# Lumiboard_-_main_board_rev_C.net
KiCad netlist of a schematic drawn in EAGLE
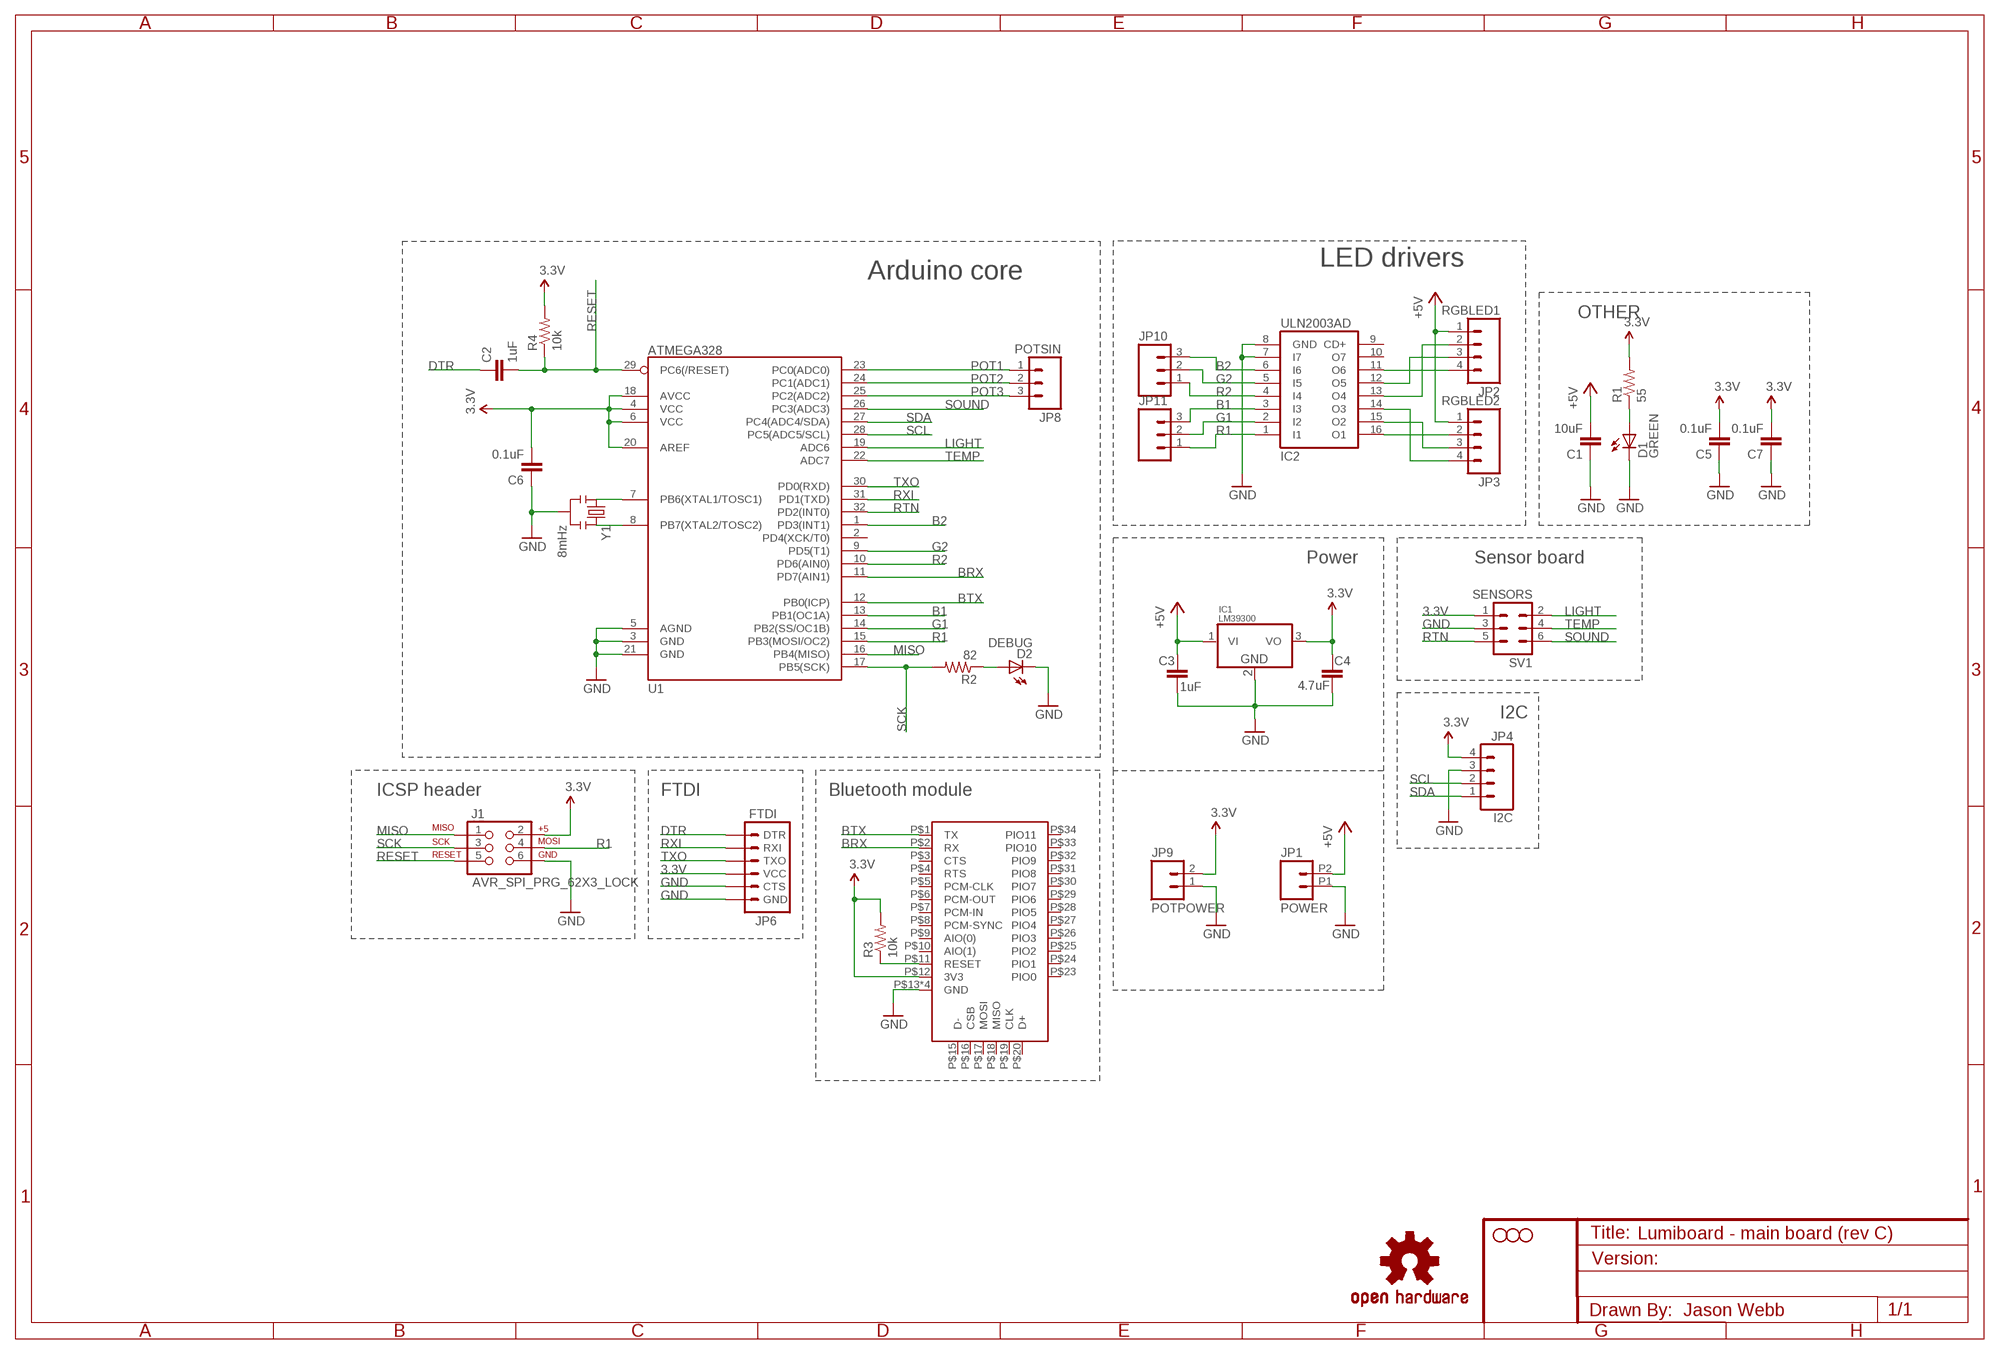
[diagram p0: schematic, sheet 1]

(export (version "E")
  (design (tool "Eeschema 10.0.6"))
  (components
    (comp (ref "C1")
      (value "10uF")
      (footprint "eagle-import:0805")
      (libsource (lib "eagle-import") (part "CAP0805"))
    )
    (comp (ref "C2")
      (value "1uF")
      (footprint "eagle-import:0805")
      (libsource (lib "eagle-import") (part "CAP0805"))
    )
    (comp (ref "C3")
      (value "1uF")
      (footprint "eagle-import:0805")
      (libsource (lib "eagle-import") (part "CAP0805"))
    )
    (comp (ref "C4")
      (value "4.7uF")
      (footprint "eagle-import:0805")
      (libsource (lib "eagle-import") (part "CAP0805"))
    )
    (comp (ref "C5")
      (value "0.1uF")
      (footprint "eagle-import:0805")
      (libsource (lib "eagle-import") (part "CAP0805"))
    )
    (comp (ref "C6")
      (value "0.1uF")
      (footprint "eagle-import:0805")
      (libsource (lib "eagle-import") (part "CAP0805"))
    )
    (comp (ref "C7")
      (value "0.1uF")
      (footprint "eagle-import:0805")
      (libsource (lib "eagle-import") (part "CAP0805"))
    )
    (comp (ref "D1")
      (value "GREEN")
      (footprint "eagle-import:CHIPLED_0805")
      (libsource (lib "eagle-import") (part "LEDCHIPLED_0805"))
    )
    (comp (ref "D2")
      (value "DEBUG")
      (footprint "eagle-import:CHIPLED_0805")
      (libsource (lib "eagle-import") (part "LEDCHIPLED_0805"))
    )
    (comp (ref "H1")
      (value "STAND-OFFTIGHT")
      (footprint "eagle-import:STAND-OFF-TIGHT")
      (libsource (lib "eagle-import") (part "STAND-OFFTIGHT"))
    )
    (comp (ref "H2")
      (value "STAND-OFFTIGHT")
      (footprint "eagle-import:STAND-OFF-TIGHT")
      (libsource (lib "eagle-import") (part "STAND-OFFTIGHT"))
    )
    (comp (ref "H3")
      (value "STAND-OFFTIGHT")
      (footprint "eagle-import:STAND-OFF-TIGHT")
      (libsource (lib "eagle-import") (part "STAND-OFFTIGHT"))
    )
    (comp (ref "IC1")
      (value "LM39300")
      (footprint "eagle-import:DPAK")
      (libsource (lib "eagle-import") (part "LM39300"))
    )
    (comp (ref "IC2")
      (value "ULN2003AD")
      (footprint "eagle-import:SO16")
      (libsource (lib "eagle-import") (part "ULN2003AD"))
    )
    (comp (ref "J1")
      (value "AVR_SPI_PRG_62X3_LOCK")
      (footprint "eagle-import:2X3_LOCK")
      (libsource (lib "eagle-import") (part "AVR_SPI_PRG_62X3_LOCK"))
    )
    (comp (ref "JP1")
      (value "POWER")
      (footprint "eagle-import:1X02_2.54_SCREWTERM")
      (libsource (lib "eagle-import") (part "M022.54MM_SCREWTERM"))
    )
    (comp (ref "JP2")
      (value "RGBLED1")
      (footprint "eagle-import:1X04")
      (libsource (lib "eagle-import") (part "M04PTH"))
    )
    (comp (ref "JP3")
      (value "RGBLED2")
      (footprint "eagle-import:1X04")
      (libsource (lib "eagle-import") (part "M04PTH"))
    )
    (comp (ref "JP4")
      (value "I2C")
      (footprint "eagle-import:1X04")
      (libsource (lib "eagle-import") (part "M04PTH"))
    )
    (comp (ref "JP6")
      (value "FTDI")
      (footprint "eagle-import:1X06_LOCK")
      (libsource (lib "eagle-import") (part "ARDUINO_SERIAL_PROGRAMLOCK"))
    )
    (comp (ref "JP8")
      (value "POTSIN")
      (footprint "eagle-import:1X03")
      (libsource (lib "eagle-import") (part "M03PTH"))
    )
    (comp (ref "JP9")
      (value "POTPOWER")
      (footprint "eagle-import:1X02")
      (libsource (lib "eagle-import") (part "M02PTH"))
    )
    (comp (ref "JP10")
      (value "M03PTH")
      (footprint "eagle-import:1X03")
      (libsource (lib "eagle-import") (part "SparkFun-Connectors_M03PTH"))
    )
    (comp (ref "JP11")
      (value "M03PTH")
      (footprint "eagle-import:1X03")
      (libsource (lib "eagle-import") (part "SparkFun-Connectors_M03PTH"))
    )
    (comp (ref "LOGO1")
      (value "OSHW-LOGOS")
      (footprint "eagle-import:OSHW-LOGO-S")
      (libsource (lib "eagle-import") (part "OSHW-LOGOS"))
    )
    (comp (ref "R1")
      (value "55")
      (footprint "eagle-import:0805")
      (libsource (lib "eagle-import") (part "RESISTOR0805-RES"))
    )
    (comp (ref "R2")
      (value "82")
      (footprint "eagle-import:0805")
      (libsource (lib "eagle-import") (part "RESISTOR0805-RES"))
    )
    (comp (ref "R3")
      (value "10k")
      (footprint "eagle-import:0805")
      (libsource (lib "eagle-import") (part "RESISTOR0805-RES"))
    )
    (comp (ref "R4")
      (value "10k")
      (footprint "eagle-import:0805")
      (libsource (lib "eagle-import") (part "RESISTOR0805-RES"))
    )
    (comp (ref "SV1")
      (value "SENSORS")
      (footprint "eagle-import:ML6")
      (libsource (lib "eagle-import") (part "ML6"))
    )
    (comp (ref "U1")
      (value "ATMEGA328")
      (footprint "eagle-import:TQFP32-08")
      (libsource (lib "eagle-import") (part "ATMEGA168"))
    )
    (comp (ref "U2")
      (value "DX_BT_MODULE")
      (footprint "eagle-import:DXBLUETOOTHMODULE")
      (libsource (lib "eagle-import") (part "DX_BT_MODULE"))
    )
    (comp (ref "Y1")
      (value "8mHz")
      (footprint "eagle-import:RESONATOR-SMD")
      (libsource (lib "eagle-import") (part "RESONATORSMD"))
    )
  )
  (nets
    (net (code "1") (name "+5V") (class "Default")
      (node (ref "C1") (pin "2") (pinfunction "2_2") (pintype "passive"))
      (node (ref "C3") (pin "2") (pinfunction "2_2") (pintype "passive"))
      (node (ref "IC1") (pin "1") (pinfunction "VI_1") (pintype "input"))
      (node (ref "JP1") (pin "P2") (pinfunction "2_P2") (pintype "passive"))
      (node (ref "JP2") (pin "1") (pinfunction "1_1") (pintype "passive"))
      (node (ref "JP3") (pin "1") (pinfunction "1_1") (pintype "passive"))
    )
    (net (code "2") (name "/B1") (class "Default")
      (node (ref "IC2") (pin "3") (pinfunction "I3_3") (pintype "input"))
      (node (ref "JP11") (pin "3") (pinfunction "3_3") (pintype "passive"))
      (node (ref "U1") (pin "13") (pinfunction "PB1(OC1A)_13") (pintype "bidirectional"))
    )
    (net (code "3") (name "/B2") (class "Default")
      (node (ref "IC2") (pin "6") (pinfunction "I6_6") (pintype "input"))
      (node (ref "JP10") (pin "3") (pinfunction "3_3") (pintype "passive"))
      (node (ref "U1") (pin "1") (pinfunction "PD3(INT1)_1") (pintype "bidirectional"))
    )
    (net (code "4") (name "/BRX") (class "Default")
      (node (ref "U1") (pin "11") (pinfunction "PD7(AIN1)_11") (pintype "bidirectional"))
      (node (ref "U2") (pin "P$2") (pinfunction "RX_P$2") (pintype "input"))
    )
    (net (code "5") (name "/BTX") (class "Default")
      (node (ref "U1") (pin "12") (pinfunction "PB0(ICP)_12") (pintype "bidirectional"))
      (node (ref "U2") (pin "P$1") (pinfunction "TX_P$1") (pintype "output"))
    )
    (net (code "6") (name "/DTR") (class "Default")
      (node (ref "C2") (pin "1") (pinfunction "1_1") (pintype "passive"))
      (node (ref "JP6") (pin "1") (pinfunction "DTR_1") (pintype "passive"))
    )
    (net (code "7") (name "/G1") (class "Default")
      (node (ref "IC2") (pin "2") (pinfunction "I2_2") (pintype "input"))
      (node (ref "JP11") (pin "2") (pinfunction "2_2") (pintype "passive"))
      (node (ref "U1") (pin "14") (pinfunction "PB2(SS/OC1B)_14") (pintype "bidirectional"))
    )
    (net (code "8") (name "/G2") (class "Default")
      (node (ref "IC2") (pin "5") (pinfunction "I5_5") (pintype "input"))
      (node (ref "JP10") (pin "2") (pinfunction "2_2") (pintype "passive"))
      (node (ref "U1") (pin "9") (pinfunction "PD5(T1)_9") (pintype "bidirectional"))
    )
    (net (code "9") (name "/LIGHT") (class "Default")
      (node (ref "SV1") (pin "2") (pinfunction "2_2") (pintype "passive"))
      (node (ref "U1") (pin "19") (pinfunction "ADC6_19") (pintype "bidirectional"))
    )
    (net (code "10") (name "/MISO") (class "Default")
      (node (ref "J1") (pin "1") (pinfunction "1_1") (pintype "passive"))
      (node (ref "U1") (pin "16") (pinfunction "PB4(MISO)_16") (pintype "bidirectional"))
    )
    (net (code "11") (name "/POT1") (class "Default")
      (node (ref "JP8") (pin "1") (pinfunction "1_1") (pintype "passive"))
      (node (ref "U1") (pin "23") (pinfunction "PC0(ADC0)_23") (pintype "bidirectional"))
    )
    (net (code "12") (name "/POT2") (class "Default")
      (node (ref "JP8") (pin "2") (pinfunction "2_2") (pintype "passive"))
      (node (ref "U1") (pin "24") (pinfunction "PC1(ADC1)_24") (pintype "bidirectional"))
    )
    (net (code "13") (name "/POT3") (class "Default")
      (node (ref "JP8") (pin "3") (pinfunction "3_3") (pintype "passive"))
      (node (ref "U1") (pin "25") (pinfunction "PC2(ADC2)_25") (pintype "bidirectional"))
    )
    (net (code "14") (name "/R1") (class "Default")
      (node (ref "IC2") (pin "1") (pinfunction "I1_1") (pintype "input"))
      (node (ref "J1") (pin "4") (pinfunction "4_4") (pintype "passive"))
      (node (ref "JP11") (pin "1") (pinfunction "1_1") (pintype "passive"))
      (node (ref "U1") (pin "15") (pinfunction "PB3(MOSI/OC2)_15") (pintype "bidirectional"))
    )
    (net (code "15") (name "/R2") (class "Default")
      (node (ref "IC2") (pin "4") (pinfunction "I4_4") (pintype "input"))
      (node (ref "JP10") (pin "1") (pinfunction "1_1") (pintype "passive"))
      (node (ref "U1") (pin "10") (pinfunction "PD6(AIN0)_10") (pintype "bidirectional"))
    )
    (net (code "16") (name "/RESET") (class "Default")
      (node (ref "C2") (pin "2") (pinfunction "2_2") (pintype "passive"))
      (node (ref "J1") (pin "5") (pinfunction "5_5") (pintype "passive"))
      (node (ref "R4") (pin "1") (pinfunction "1_1") (pintype "passive"))
      (node (ref "U1") (pin "29") (pinfunction "PC6(/RESET)_29") (pintype "bidirectional"))
    )
    (net (code "17") (name "/RTN") (class "Default")
      (node (ref "SV1") (pin "5") (pinfunction "5_5") (pintype "passive"))
      (node (ref "U1") (pin "32") (pinfunction "PD2(INT0)_32") (pintype "bidirectional"))
    )
    (net (code "18") (name "/RXI") (class "Default")
      (node (ref "JP6") (pin "2") (pinfunction "RXI_2") (pintype "passive"))
      (node (ref "U1") (pin "31") (pinfunction "PD1(TXD)_31") (pintype "bidirectional"))
    )
    (net (code "19") (name "/SCK") (class "Default")
      (node (ref "J1") (pin "3") (pinfunction "3_3") (pintype "passive"))
      (node (ref "R2") (pin "2") (pinfunction "2_2") (pintype "passive"))
      (node (ref "U1") (pin "17") (pinfunction "PB5(SCK)_17") (pintype "bidirectional"))
    )
    (net (code "20") (name "/SCL") (class "Default")
      (node (ref "JP4") (pin "2") (pinfunction "2_2") (pintype "passive"))
      (node (ref "U1") (pin "28") (pinfunction "PC5(ADC5/SCL)_28") (pintype "bidirectional"))
    )
    (net (code "21") (name "/SDA") (class "Default")
      (node (ref "JP4") (pin "1") (pinfunction "1_1") (pintype "passive"))
      (node (ref "U1") (pin "27") (pinfunction "PC4(ADC4/SDA)_27") (pintype "bidirectional"))
    )
    (net (code "22") (name "/SOUND") (class "Default")
      (node (ref "SV1") (pin "6") (pinfunction "6_6") (pintype "passive"))
      (node (ref "U1") (pin "26") (pinfunction "PC3(ADC3)_26") (pintype "bidirectional"))
    )
    (net (code "23") (name "/TEMP") (class "Default")
      (node (ref "SV1") (pin "4") (pinfunction "4_4") (pintype "passive"))
      (node (ref "U1") (pin "22") (pinfunction "ADC7_22") (pintype "bidirectional"))
    )
    (net (code "24") (name "/TXO") (class "Default")
      (node (ref "JP6") (pin "3") (pinfunction "TXO_3") (pintype "passive"))
      (node (ref "U1") (pin "30") (pinfunction "PD0(RXD)_30") (pintype "bidirectional"))
    )
    (net (code "25") (name "3.3V") (class "Default")
      (node (ref "C4") (pin "2") (pinfunction "2_2") (pintype "passive"))
      (node (ref "C5") (pin "2") (pinfunction "2_2") (pintype "passive"))
      (node (ref "C6") (pin "2") (pinfunction "2_2") (pintype "passive"))
      (node (ref "C7") (pin "2") (pinfunction "2_2") (pintype "passive"))
      (node (ref "IC1") (pin "3") (pinfunction "VO_3") (pintype "bidirectional"))
      (node (ref "J1") (pin "2") (pinfunction "2_2") (pintype "passive"))
      (node (ref "JP4") (pin "4") (pinfunction "4_4") (pintype "passive"))
      (node (ref "JP6") (pin "4") (pinfunction "VCC_4") (pintype "passive"))
      (node (ref "JP9") (pin "2") (pinfunction "2_2") (pintype "passive"))
      (node (ref "R1") (pin "2") (pinfunction "2_2") (pintype "passive"))
      (node (ref "R3") (pin "2") (pinfunction "2_2") (pintype "passive"))
      (node (ref "R4") (pin "2") (pinfunction "2_2") (pintype "passive"))
      (node (ref "SV1") (pin "1") (pinfunction "1_1") (pintype "passive"))
      (node (ref "U1") (pin "18") (pinfunction "AVCC_18") (pintype "bidirectional"))
      (node (ref "U1") (pin "20") (pinfunction "AREF_20") (pintype "bidirectional"))
      (node (ref "U1") (pin "4") (pinfunction "VCC_4") (pintype "bidirectional"))
      (node (ref "U1") (pin "6") (pinfunction "VCC_6") (pintype "bidirectional"))
      (node (ref "U2") (pin "P$12") (pinfunction "3V3_P$12") (pintype "power_in"))
    )
    (net (code "26") (name "GND") (class "Default")
      (node (ref "C1") (pin "1") (pinfunction "1_1") (pintype "passive"))
      (node (ref "C3") (pin "1") (pinfunction "1_1") (pintype "passive"))
      (node (ref "C4") (pin "1") (pinfunction "1_1") (pintype "passive"))
      (node (ref "C5") (pin "1") (pinfunction "1_1") (pintype "passive"))
      (node (ref "C6") (pin "1") (pinfunction "1_1") (pintype "passive"))
      (node (ref "C7") (pin "1") (pinfunction "1_1") (pintype "passive"))
      (node (ref "D1") (pin "C") (pinfunction "C_C") (pintype "passive"))
      (node (ref "D2") (pin "C") (pinfunction "C_C") (pintype "passive"))
      (node (ref "IC1") (pin "2") (pinfunction "GND_2") (pintype "bidirectional"))
      (node (ref "IC2") (pin "7") (pinfunction "I7_7") (pintype "input"))
      (node (ref "IC2") (pin "8") (pinfunction "GND_8") (pintype "power_in"))
      (node (ref "J1") (pin "6") (pinfunction "6_6") (pintype "passive"))
      (node (ref "JP1") (pin "P1") (pinfunction "1_P1") (pintype "passive"))
      (node (ref "JP4") (pin "3") (pinfunction "3_3") (pintype "passive"))
      (node (ref "JP6") (pin "5") (pinfunction "CTS_5") (pintype "passive"))
      (node (ref "JP6") (pin "6") (pinfunction "GND_6") (pintype "passive"))
      (node (ref "JP9") (pin "1") (pinfunction "1_1") (pintype "passive"))
      (node (ref "SV1") (pin "3") (pinfunction "3_3") (pintype "passive"))
      (node (ref "U1") (pin "21") (pinfunction "GND_21") (pintype "bidirectional"))
      (node (ref "U1") (pin "3") (pinfunction "GND_3") (pintype "bidirectional"))
      (node (ref "U1") (pin "5") (pinfunction "AGND_5") (pintype "bidirectional"))
      (node (ref "U2") (pin "P$13") (pinfunction "GND_P$13") (pintype "power_in"))
      (node (ref "U2") (pin "P$14") (pinfunction "GND_P$14") (pintype "power_in"))
      (node (ref "U2") (pin "P$21") (pinfunction "GND_P$21") (pintype "power_in"))
      (node (ref "U2") (pin "P$22") (pinfunction "GND_P$22") (pintype "power_in"))
      (node (ref "Y1") (pin "2") (pinfunction "2_2") (pintype "passive"))
    )
    (net (code "27") (name "Net-(D1-PadA)") (class "Default")
      (node (ref "D1") (pin "A") (pinfunction "A_A") (pintype "passive"))
      (node (ref "R1") (pin "1") (pinfunction "1_1") (pintype "passive"))
    )
    (net (code "28") (name "Net-(D2-PadA)") (class "Default")
      (node (ref "D2") (pin "A") (pinfunction "A_A") (pintype "passive"))
      (node (ref "R2") (pin "1") (pinfunction "1_1") (pintype "passive"))
    )
    (net (code "29") (name "Net-(IC2-O1)") (class "Default")
      (node (ref "IC2") (pin "16") (pinfunction "O1_16") (pintype "open_collector"))
      (node (ref "JP3") (pin "2") (pinfunction "2_2") (pintype "passive"))
    )
    (net (code "30") (name "Net-(IC2-O2)") (class "Default")
      (node (ref "IC2") (pin "15") (pinfunction "O2_15") (pintype "open_collector"))
      (node (ref "JP3") (pin "3") (pinfunction "3_3") (pintype "passive"))
    )
    (net (code "31") (name "Net-(IC2-O3)") (class "Default")
      (node (ref "IC2") (pin "14") (pinfunction "O3_14") (pintype "open_collector"))
      (node (ref "JP3") (pin "4") (pinfunction "4_4") (pintype "passive"))
    )
    (net (code "32") (name "Net-(IC2-O4)") (class "Default")
      (node (ref "IC2") (pin "13") (pinfunction "O4_13") (pintype "open_collector"))
      (node (ref "JP2") (pin "2") (pinfunction "2_2") (pintype "passive"))
    )
    (net (code "33") (name "Net-(IC2-O5)") (class "Default")
      (node (ref "IC2") (pin "12") (pinfunction "O5_12") (pintype "open_collector"))
      (node (ref "JP2") (pin "3") (pinfunction "3_3") (pintype "passive"))
    )
    (net (code "34") (name "Net-(IC2-O6)") (class "Default")
      (node (ref "IC2") (pin "11") (pinfunction "O6_11") (pintype "open_collector"))
      (node (ref "JP2") (pin "4") (pinfunction "4_4") (pintype "passive"))
    )
    (net (code "35") (name "Net-(U1-PB6(XTAL1{slash}TOSC1))") (class "Default")
      (node (ref "U1") (pin "7") (pinfunction "PB6(XTAL1/TOSC1)_7") (pintype "bidirectional"))
      (node (ref "Y1") (pin "1") (pinfunction "1_1") (pintype "passive"))
    )
    (net (code "36") (name "Net-(U1-PB7(XTAL2{slash}TOSC2))") (class "Default")
      (node (ref "U1") (pin "8") (pinfunction "PB7(XTAL2/TOSC2)_8") (pintype "bidirectional"))
      (node (ref "Y1") (pin "3") (pinfunction "3_3") (pintype "passive"))
    )
    (net (code "37") (name "Net-(U2-RESET)") (class "Default")
      (node (ref "R3") (pin "1") (pinfunction "1_1") (pintype "passive"))
      (node (ref "U2") (pin "P$11") (pinfunction "RESET_P$11") (pintype "input"))
    )
    (net (code "38") (name "unconnected-(IC2-CD+-Pad9)") (class "Default")
      (node (ref "IC2") (pin "9") (pinfunction "CD+_9") (pintype "passive"))
    )
    (net (code "39") (name "unconnected-(IC2-O7-Pad10)") (class "Default")
      (node (ref "IC2") (pin "10") (pinfunction "O7_10") (pintype "open_collector"))
    )
    (net (code "40") (name "unconnected-(U1-PD4(XCK{slash}T0)-Pad2)") (class "Default")
      (node (ref "U1") (pin "2") (pinfunction "PD4(XCK/T0)_2") (pintype "bidirectional"))
    )
    (net (code "41") (name "unconnected-(U2-AIO(0)-PadP$9)") (class "Default")
      (node (ref "U2") (pin "P$9") (pinfunction "AIO(0)_P$9") (pintype "bidirectional"))
    )
    (net (code "42") (name "unconnected-(U2-AIO(1)-PadP$10)") (class "Default")
      (node (ref "U2") (pin "P$10") (pinfunction "AIO(1)_P$10") (pintype "bidirectional"))
    )
    (net (code "43") (name "unconnected-(U2-CLK-PadP$19)") (class "Default")
      (node (ref "U2") (pin "P$19") (pinfunction "CLK_P$19") (pintype "input"))
    )
    (net (code "44") (name "unconnected-(U2-CSB-PadP$16)") (class "Default")
      (node (ref "U2") (pin "P$16") (pinfunction "CSB_P$16") (pintype "input"))
    )
    (net (code "45") (name "unconnected-(U2-CTS-PadP$3)") (class "Default")
      (node (ref "U2") (pin "P$3") (pinfunction "CTS_P$3") (pintype "input"))
    )
    (net (code "46") (name "unconnected-(U2-D+-PadP$20)") (class "Default")
      (node (ref "U2") (pin "P$20") (pinfunction "D+_P$20") (pintype "bidirectional"))
    )
    (net (code "47") (name "unconnected-(U2-D--PadP$15)") (class "Default")
      (node (ref "U2") (pin "P$15") (pinfunction "D-_P$15") (pintype "bidirectional"))
    )
    (net (code "48") (name "unconnected-(U2-MISO-PadP$18)") (class "Default")
      (node (ref "U2") (pin "P$18") (pinfunction "MISO_P$18") (pintype "output"))
    )
    (net (code "49") (name "unconnected-(U2-MOSI-PadP$17)") (class "Default")
      (node (ref "U2") (pin "P$17") (pinfunction "MOSI_P$17") (pintype "input"))
    )
    (net (code "50") (name "unconnected-(U2-PCM-CLK-PadP$5)") (class "Default")
      (node (ref "U2") (pin "P$5") (pinfunction "PCM-CLK_P$5") (pintype "bidirectional"))
    )
    (net (code "51") (name "unconnected-(U2-PCM-IN-PadP$7)") (class "Default")
      (node (ref "U2") (pin "P$7") (pinfunction "PCM-IN_P$7") (pintype "input"))
    )
    (net (code "52") (name "unconnected-(U2-PCM-OUT-PadP$6)") (class "Default")
      (node (ref "U2") (pin "P$6") (pinfunction "PCM-OUT_P$6") (pintype "output"))
    )
    (net (code "53") (name "unconnected-(U2-PCM-SYNC-PadP$8)") (class "Default")
      (node (ref "U2") (pin "P$8") (pinfunction "PCM-SYNC_P$8") (pintype "bidirectional"))
    )
    (net (code "54") (name "unconnected-(U2-PIO0-PadP$23)") (class "Default")
      (node (ref "U2") (pin "P$23") (pinfunction "PIO0_P$23") (pintype "bidirectional"))
    )
    (net (code "55") (name "unconnected-(U2-PIO1-PadP$24)") (class "Default")
      (node (ref "U2") (pin "P$24") (pinfunction "PIO1_P$24") (pintype "bidirectional"))
    )
    (net (code "56") (name "unconnected-(U2-PIO2-PadP$25)") (class "Default")
      (node (ref "U2") (pin "P$25") (pinfunction "PIO2_P$25") (pintype "bidirectional"))
    )
    (net (code "57") (name "unconnected-(U2-PIO3-PadP$26)") (class "Default")
      (node (ref "U2") (pin "P$26") (pinfunction "PIO3_P$26") (pintype "bidirectional"))
    )
    (net (code "58") (name "unconnected-(U2-PIO4-PadP$27)") (class "Default")
      (node (ref "U2") (pin "P$27") (pinfunction "PIO4_P$27") (pintype "bidirectional"))
    )
    (net (code "59") (name "unconnected-(U2-PIO5-PadP$28)") (class "Default")
      (node (ref "U2") (pin "P$28") (pinfunction "PIO5_P$28") (pintype "bidirectional"))
    )
    (net (code "60") (name "unconnected-(U2-PIO6-PadP$29)") (class "Default")
      (node (ref "U2") (pin "P$29") (pinfunction "PIO6_P$29") (pintype "bidirectional"))
    )
    (net (code "61") (name "unconnected-(U2-PIO7-PadP$30)") (class "Default")
      (node (ref "U2") (pin "P$30") (pinfunction "PIO7_P$30") (pintype "bidirectional"))
    )
    (net (code "62") (name "unconnected-(U2-PIO8-PadP$31)") (class "Default")
      (node (ref "U2") (pin "P$31") (pinfunction "PIO8_P$31") (pintype "bidirectional"))
    )
    (net (code "63") (name "unconnected-(U2-PIO9-PadP$32)") (class "Default")
      (node (ref "U2") (pin "P$32") (pinfunction "PIO9_P$32") (pintype "bidirectional"))
    )
    (net (code "64") (name "unconnected-(U2-PIO10-PadP$33)") (class "Default")
      (node (ref "U2") (pin "P$33") (pinfunction "PIO10_P$33") (pintype "bidirectional"))
    )
    (net (code "65") (name "unconnected-(U2-PIO11-PadP$34)") (class "Default")
      (node (ref "U2") (pin "P$34") (pinfunction "PIO11_P$34") (pintype "bidirectional"))
    )
    (net (code "66") (name "unconnected-(U2-RTS-PadP$4)") (class "Default")
      (node (ref "U2") (pin "P$4") (pinfunction "RTS_P$4") (pintype "output"))
    )
  )
)
